# frequency_divider_controller.net
KiCad netlist of a schematic drawn in EAGLE
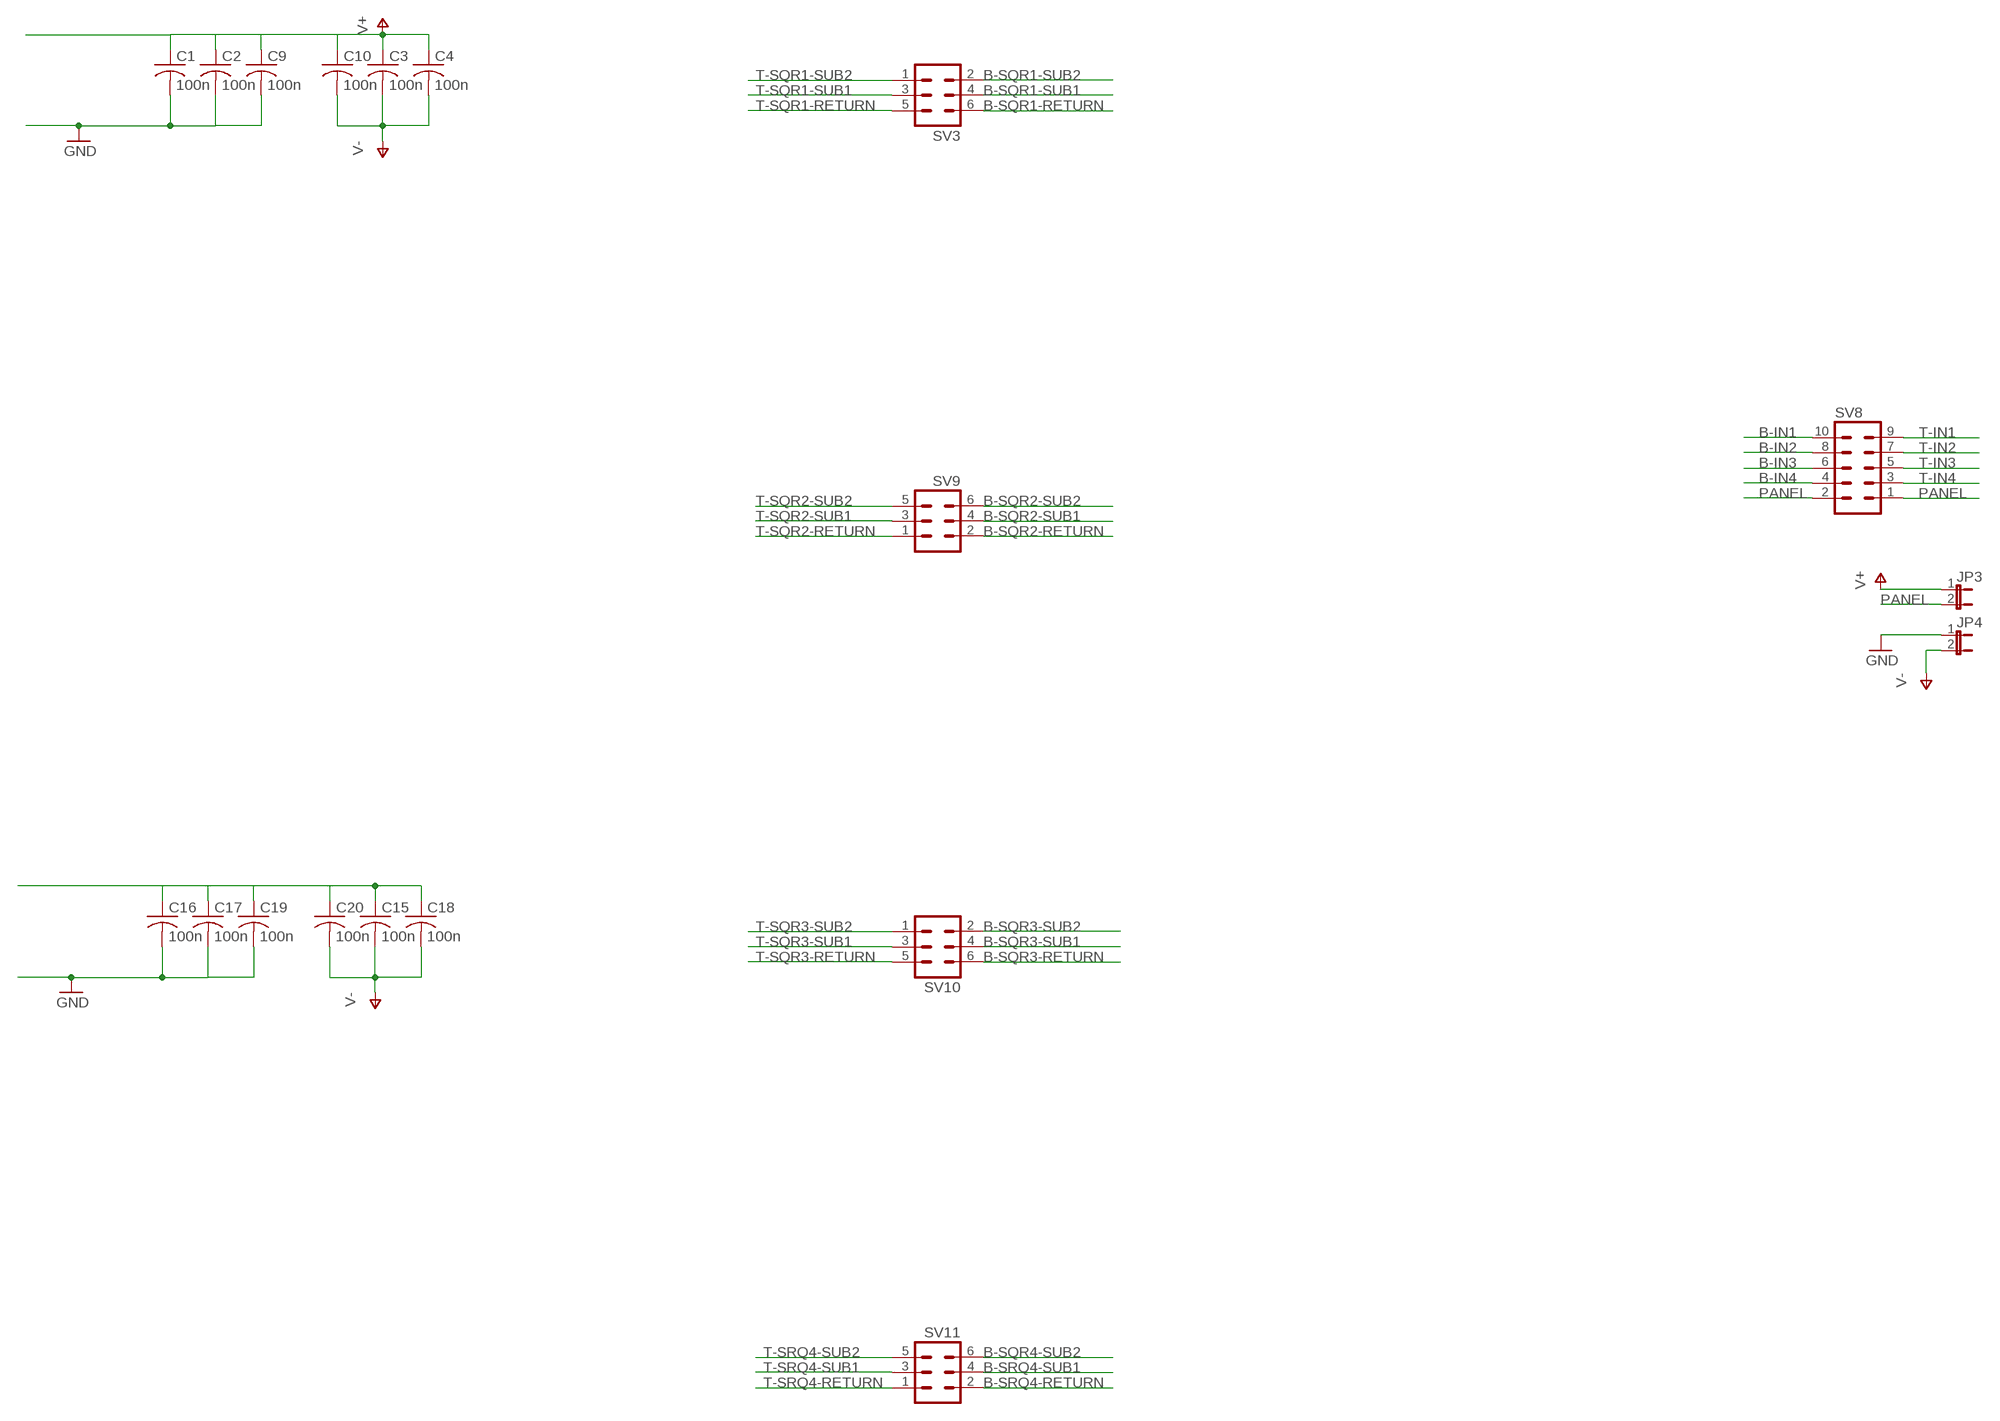
[diagram p0: schematic, sheet 1]

(export (version "E")
  (design (tool "Eeschema 10.0.6"))
  (components
    (comp (ref "C1")
      (value "100n")
      (footprint "eagle-import:C025-024X044")
      (libsource (lib "eagle-import") (part "C-US025-024X044"))
    )
    (comp (ref "C2")
      (value "100n")
      (footprint "eagle-import:C025-024X044")
      (libsource (lib "eagle-import") (part "C-US025-024X044"))
    )
    (comp (ref "C3")
      (value "100n")
      (footprint "eagle-import:C025-024X044")
      (libsource (lib "eagle-import") (part "C-US025-024X044"))
    )
    (comp (ref "C4")
      (value "100n")
      (footprint "eagle-import:C025-024X044")
      (libsource (lib "eagle-import") (part "C-US025-024X044"))
    )
    (comp (ref "C9")
      (value "100n")
      (footprint "eagle-import:C025-024X044")
      (libsource (lib "eagle-import") (part "C-US025-024X044"))
    )
    (comp (ref "C10")
      (value "100n")
      (footprint "eagle-import:C025-024X044")
      (libsource (lib "eagle-import") (part "C-US025-024X044"))
    )
    (comp (ref "C15")
      (value "100n")
      (footprint "eagle-import:C025-024X044")
      (libsource (lib "eagle-import") (part "C-US025-024X044"))
    )
    (comp (ref "C16")
      (value "100n")
      (footprint "eagle-import:C025-024X044")
      (libsource (lib "eagle-import") (part "C-US025-024X044"))
    )
    (comp (ref "C17")
      (value "100n")
      (footprint "eagle-import:C025-024X044")
      (libsource (lib "eagle-import") (part "C-US025-024X044"))
    )
    (comp (ref "C18")
      (value "100n")
      (footprint "eagle-import:C025-024X044")
      (libsource (lib "eagle-import") (part "C-US025-024X044"))
    )
    (comp (ref "C19")
      (value "100n")
      (footprint "eagle-import:C025-024X044")
      (libsource (lib "eagle-import") (part "C-US025-024X044"))
    )
    (comp (ref "C20")
      (value "100n")
      (footprint "eagle-import:C025-024X044")
      (libsource (lib "eagle-import") (part "C-US025-024X044"))
    )
    (comp (ref "JP3")
      (value "JP1E")
      (footprint "eagle-import:JP1")
      (libsource (lib "eagle-import") (part "JP1E"))
    )
    (comp (ref "JP4")
      (value "JP1E")
      (footprint "eagle-import:JP1")
      (libsource (lib "eagle-import") (part "JP1E"))
    )
    (comp (ref "SV3")
      (value "MA03-2")
      (footprint "eagle-import:MA03-2")
      (libsource (lib "eagle-import") (part "MA03-2"))
    )
    (comp (ref "SV8")
      (value "MA05-2")
      (footprint "eagle-import:MA05-2")
      (libsource (lib "eagle-import") (part "MA05-2"))
    )
    (comp (ref "SV9")
      (value "MA03-2")
      (footprint "eagle-import:MA03-2")
      (libsource (lib "eagle-import") (part "MA03-2"))
    )
    (comp (ref "SV10")
      (value "MA03-2")
      (footprint "eagle-import:MA03-2")
      (libsource (lib "eagle-import") (part "MA03-2"))
    )
    (comp (ref "SV11")
      (value "MA03-2")
      (footprint "eagle-import:MA03-2")
      (libsource (lib "eagle-import") (part "MA03-2"))
    )
  )
  (nets
    (net (code "1") (name "/B-IN1") (class "Default")
      (node (ref "SV8") (pin "10") (pinfunction "10_10") (pintype "passive"))
    )
    (net (code "2") (name "/B-IN2") (class "Default")
      (node (ref "SV8") (pin "8") (pinfunction "8_8") (pintype "passive"))
    )
    (net (code "3") (name "/B-IN3") (class "Default")
      (node (ref "SV8") (pin "6") (pinfunction "6_6") (pintype "passive"))
    )
    (net (code "4") (name "/B-IN4") (class "Default")
      (node (ref "SV8") (pin "4") (pinfunction "4_4") (pintype "passive"))
    )
    (net (code "5") (name "/B-SQR1-RETURN") (class "Default")
      (node (ref "SV3") (pin "6") (pinfunction "6_6") (pintype "passive"))
    )
    (net (code "6") (name "/B-SQR1-SUB1") (class "Default")
      (node (ref "SV3") (pin "4") (pinfunction "4_4") (pintype "passive"))
    )
    (net (code "7") (name "/B-SQR1-SUB2") (class "Default")
      (node (ref "SV3") (pin "2") (pinfunction "2_2") (pintype "passive"))
    )
    (net (code "8") (name "/B-SQR2-RETURN") (class "Default")
      (node (ref "SV9") (pin "2") (pinfunction "2_2") (pintype "passive"))
    )
    (net (code "9") (name "/B-SQR2-SUB1") (class "Default")
      (node (ref "SV9") (pin "4") (pinfunction "4_4") (pintype "passive"))
    )
    (net (code "10") (name "/B-SQR2-SUB2") (class "Default")
      (node (ref "SV9") (pin "6") (pinfunction "6_6") (pintype "passive"))
    )
    (net (code "11") (name "/B-SQR3-RETURN") (class "Default")
      (node (ref "SV10") (pin "6") (pinfunction "6_6") (pintype "passive"))
    )
    (net (code "12") (name "/B-SQR3-SUB1") (class "Default")
      (node (ref "SV10") (pin "4") (pinfunction "4_4") (pintype "passive"))
    )
    (net (code "13") (name "/B-SQR3-SUB2") (class "Default")
      (node (ref "SV10") (pin "2") (pinfunction "2_2") (pintype "passive"))
    )
    (net (code "14") (name "/B-SQR4-SUB2") (class "Default")
      (node (ref "SV11") (pin "6") (pinfunction "6_6") (pintype "passive"))
    )
    (net (code "15") (name "/B-SRQ4-RETURN") (class "Default")
      (node (ref "SV11") (pin "2") (pinfunction "2_2") (pintype "passive"))
    )
    (net (code "16") (name "/B-SRQ4-SUB1") (class "Default")
      (node (ref "SV11") (pin "4") (pinfunction "4_4") (pintype "passive"))
    )
    (net (code "17") (name "/PANEL") (class "Default")
      (node (ref "JP3") (pin "2") (pinfunction "2_2") (pintype "passive"))
      (node (ref "SV8") (pin "1") (pinfunction "1_1") (pintype "passive"))
      (node (ref "SV8") (pin "2") (pinfunction "2_2") (pintype "passive"))
    )
    (net (code "18") (name "/T-IN1") (class "Default")
      (node (ref "SV8") (pin "9") (pinfunction "9_9") (pintype "passive"))
    )
    (net (code "19") (name "/T-IN2") (class "Default")
      (node (ref "SV8") (pin "7") (pinfunction "7_7") (pintype "passive"))
    )
    (net (code "20") (name "/T-IN3") (class "Default")
      (node (ref "SV8") (pin "5") (pinfunction "5_5") (pintype "passive"))
    )
    (net (code "21") (name "/T-IN4") (class "Default")
      (node (ref "SV8") (pin "3") (pinfunction "3_3") (pintype "passive"))
    )
    (net (code "22") (name "/T-SQR1-RETURN") (class "Default")
      (node (ref "SV3") (pin "5") (pinfunction "5_5") (pintype "passive"))
    )
    (net (code "23") (name "/T-SQR1-SUB1") (class "Default")
      (node (ref "SV3") (pin "3") (pinfunction "3_3") (pintype "passive"))
    )
    (net (code "24") (name "/T-SQR1-SUB2") (class "Default")
      (node (ref "SV3") (pin "1") (pinfunction "1_1") (pintype "passive"))
    )
    (net (code "25") (name "/T-SQR2-RETURN") (class "Default")
      (node (ref "SV9") (pin "1") (pinfunction "1_1") (pintype "passive"))
    )
    (net (code "26") (name "/T-SQR2-SUB1") (class "Default")
      (node (ref "SV9") (pin "3") (pinfunction "3_3") (pintype "passive"))
    )
    (net (code "27") (name "/T-SQR2-SUB2") (class "Default")
      (node (ref "SV9") (pin "5") (pinfunction "5_5") (pintype "passive"))
    )
    (net (code "28") (name "/T-SQR3-RETURN") (class "Default")
      (node (ref "SV10") (pin "5") (pinfunction "5_5") (pintype "passive"))
    )
    (net (code "29") (name "/T-SQR3-SUB1") (class "Default")
      (node (ref "SV10") (pin "3") (pinfunction "3_3") (pintype "passive"))
    )
    (net (code "30") (name "/T-SQR3-SUB2") (class "Default")
      (node (ref "SV10") (pin "1") (pinfunction "1_1") (pintype "passive"))
    )
    (net (code "31") (name "/T-SRQ4-RETURN") (class "Default")
      (node (ref "SV11") (pin "1") (pinfunction "1_1") (pintype "passive"))
    )
    (net (code "32") (name "/T-SRQ4-SUB1") (class "Default")
      (node (ref "SV11") (pin "3") (pinfunction "3_3") (pintype "passive"))
    )
    (net (code "33") (name "/T-SRQ4-SUB2") (class "Default")
      (node (ref "SV11") (pin "5") (pinfunction "5_5") (pintype "passive"))
    )
    (net (code "34") (name "GND") (class "Default")
      (node (ref "C1") (pin "2") (pinfunction "2_2") (pintype "passive"))
      (node (ref "C16") (pin "2") (pinfunction "2_2") (pintype "passive"))
      (node (ref "C17") (pin "2") (pinfunction "2_2") (pintype "passive"))
      (node (ref "C19") (pin "2") (pinfunction "2_2") (pintype "passive"))
      (node (ref "C2") (pin "2") (pinfunction "2_2") (pintype "passive"))
      (node (ref "C9") (pin "2") (pinfunction "2_2") (pintype "passive"))
      (node (ref "JP4") (pin "1") (pinfunction "1_1") (pintype "passive"))
    )
    (net (code "35") (name "Net-(C15-Pad1)") (class "Default")
      (node (ref "C15") (pin "1") (pinfunction "1_1") (pintype "passive"))
      (node (ref "C16") (pin "1") (pinfunction "1_1") (pintype "passive"))
      (node (ref "C17") (pin "1") (pinfunction "1_1") (pintype "passive"))
      (node (ref "C18") (pin "1") (pinfunction "1_1") (pintype "passive"))
      (node (ref "C19") (pin "1") (pinfunction "1_1") (pintype "passive"))
      (node (ref "C20") (pin "1") (pinfunction "1_1") (pintype "passive"))
    )
    (net (code "36") (name "V+") (class "Default")
      (node (ref "C1") (pin "1") (pinfunction "1_1") (pintype "passive"))
      (node (ref "C10") (pin "1") (pinfunction "1_1") (pintype "passive"))
      (node (ref "C2") (pin "1") (pinfunction "1_1") (pintype "passive"))
      (node (ref "C3") (pin "1") (pinfunction "1_1") (pintype "passive"))
      (node (ref "C4") (pin "1") (pinfunction "1_1") (pintype "passive"))
      (node (ref "C9") (pin "1") (pinfunction "1_1") (pintype "passive"))
      (node (ref "JP3") (pin "1") (pinfunction "1_1") (pintype "passive"))
    )
    (net (code "37") (name "V-") (class "Default")
      (node (ref "C10") (pin "2") (pinfunction "2_2") (pintype "passive"))
      (node (ref "C15") (pin "2") (pinfunction "2_2") (pintype "passive"))
      (node (ref "C18") (pin "2") (pinfunction "2_2") (pintype "passive"))
      (node (ref "C20") (pin "2") (pinfunction "2_2") (pintype "passive"))
      (node (ref "C3") (pin "2") (pinfunction "2_2") (pintype "passive"))
      (node (ref "C4") (pin "2") (pinfunction "2_2") (pintype "passive"))
      (node (ref "JP4") (pin "2") (pinfunction "2_2") (pintype "passive"))
    )
  )
)
